# STM32_QFP100_DEVELOPMENT_BOARD.net
KiCad netlist of a schematic drawn in Altium Designer
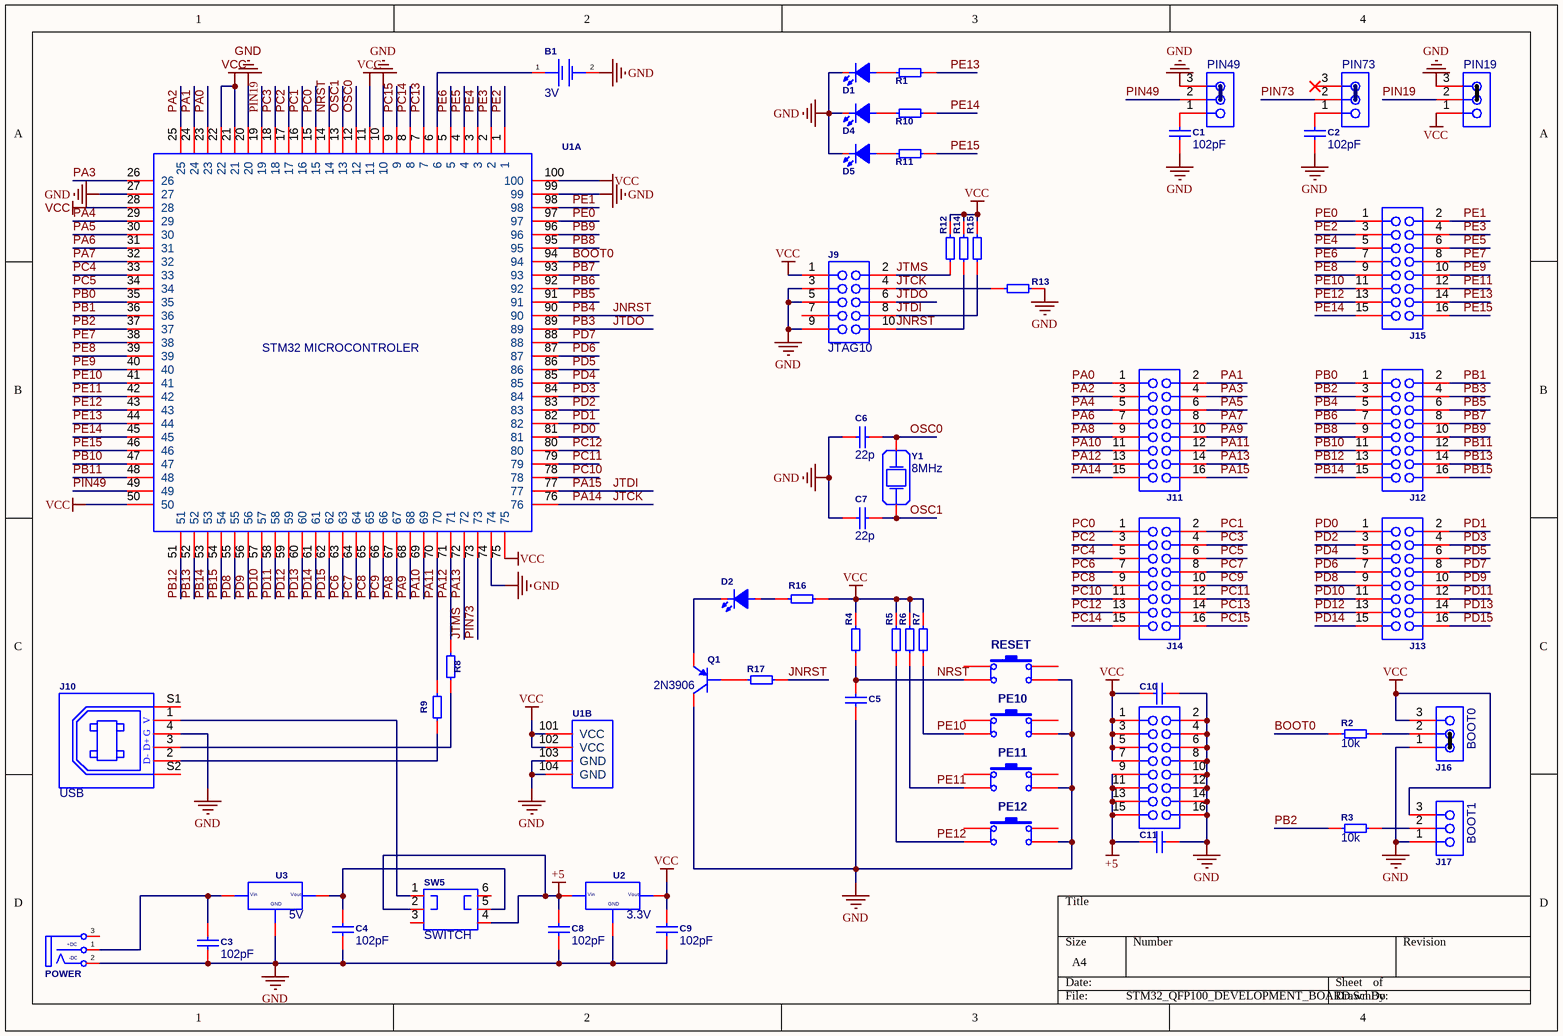
[diagram p0: STM32_QFP100_DEVELOPMENT_BOARD.SchDoc]

(export (version "E")
  (design (tool "Eeschema 10.0.6"))
  (components
    (comp (ref "B1") (value "3V") (footprint "CR1220") (libsource (lib "Lib31082020") (part "Batery")))
    (comp (ref "C1")
      (value "102pF")
      (footprint "C0805")
      (libsource (lib "Lib31082020") (part "Capacitors(SMD)"))
    )
    (comp (ref "C2")
      (value "102pF")
      (footprint "C0805")
      (libsource (lib "Lib31082020") (part "Capacitors(SMD)"))
    )
    (comp (ref "C3")
      (value "102pF")
      (footprint "C1206")
      (libsource (lib "Lib31082020") (part "Capacitors(SMD)"))
    )
    (comp (ref "C4")
      (value "102pF")
      (footprint "C1206")
      (libsource (lib "Lib31082020") (part "Capacitors(SMD)"))
    )
    (comp (ref "C5") (value "104P") (footprint "C0805") (libsource (lib "Lib31082020") (part "C0805")))
    (comp (ref "C6") (value "22p") (footprint "C0805") (libsource (lib "Lib31082020") (part "C0805")))
    (comp (ref "C7") (value "22p") (footprint "C0805") (libsource (lib "Lib31082020") (part "C0805")))
    (comp (ref "C8")
      (value "102pF")
      (footprint "C1206")
      (libsource (lib "Lib31082020") (part "Capacitors(SMD)"))
    )
    (comp (ref "C9")
      (value "102pF")
      (footprint "C1206")
      (libsource (lib "Lib31082020") (part "Capacitors(SMD)"))
    )
    (comp (ref "C10")
      (value "102pF")
      (footprint "C1206")
      (libsource (lib "Lib31082020") (part "Capacitors(SMD)"))
    )
    (comp (ref "C11")
      (value "102pF")
      (footprint "C1206")
      (libsource (lib "Lib31082020") (part "Capacitors(SMD)"))
    )
    (comp (ref "D1") (value "PE13") (footprint "L0805RED") (libsource (lib "Lib31082020") (part "LED0805")))
    (comp (ref "D2")
      (value "LED0805")
      (footprint "L0805RED")
      (libsource (lib "Lib31082020") (part "LED0805"))
    )
    (comp (ref "D4") (value "PE14") (footprint "L0805RED") (libsource (lib "Lib31082020") (part "LED0805")))
    (comp (ref "D5") (value "PE15") (footprint "L0805RED") (libsource (lib "Lib31082020") (part "LED0805")))
    (comp (ref "J1")
      (value "POWER")
      (footprint "Header 8x2 TH Pitch 2.54mm")
      (libsource (lib "Lib31082020") (part "Header 8x2 TH Pitch 2.54mm"))
    )
    (comp (ref "J3")
      (value "PIN19")
      (footprint "Header 3x1 TH Pitch 2.54mm")
      (libsource (lib "Lib31082020") (part "Header 3x1 TH Pitch 2.54mm"))
    )
    (comp (ref "J5")
      (value "PIN49")
      (footprint "Header 3x1 TH Pitch 2.54mm")
      (libsource (lib "Lib31082020") (part "Header 3x1 TH Pitch 2.54mm"))
    )
    (comp (ref "J6")
      (value "PIN73")
      (footprint "Header 3x1 TH Pitch 2.54mm")
      (libsource (lib "Lib31082020") (part "Header 3x1 TH Pitch 2.54mm"))
    )
    (comp (ref "J9")
      (value "JTAG10")
      (footprint "IDC_CONNECTOR_10x2.54")
      (libsource (lib "Lib31082020") (part "IDC_2.54_5x2"))
    )
    (comp (ref "J10")
      (value "USB")
      (footprint "USB-B-TYPE")
      (libsource (lib "Lib31082020") (part "USB B Type"))
    )
    (comp (ref "J11")
      (value "PORTA")
      (footprint "Header 8x2 TH Pitch 2.54mm")
      (libsource (lib "Lib31082020") (part "Header 8x2 TH Pitch 2.54mm"))
    )
    (comp (ref "J12")
      (value "PORTB")
      (footprint "Header 8x2 TH Pitch 2.54mm")
      (libsource (lib "Lib31082020") (part "Header 8x2 TH Pitch 2.54mm"))
    )
    (comp (ref "J13")
      (value "PORTD")
      (footprint "Header 8x2 TH Pitch 2.54mm")
      (libsource (lib "Lib31082020") (part "Header 8x2 TH Pitch 2.54mm"))
    )
    (comp (ref "J14")
      (value "PORTC")
      (footprint "Header 8x2 TH Pitch 2.54mm")
      (libsource (lib "Lib31082020") (part "Header 8x2 TH Pitch 2.54mm"))
    )
    (comp (ref "J15")
      (value "PORTE")
      (footprint "Header 8x2 TH Pitch 2.54mm")
      (libsource (lib "Lib31082020") (part "Header 8x2 TH Pitch 2.54mm"))
    )
    (comp (ref "J16")
      (value "BOOT0")
      (footprint "Header 3x1 TH Pitch 2.54mm")
      (libsource (lib "Lib31082020") (part "Header 3x1 TH Pitch 2.54mm"))
    )
    (comp (ref "J17")
      (value "BOOT1")
      (footprint "Header 3x1 TH Pitch 2.54mm")
      (libsource (lib "Lib31082020") (part "Header 3x1 TH Pitch 2.54mm"))
    )
    (comp (ref "POWER")
      (value "Connector")
      (footprint "DC_K375A_Power")
      (libsource (lib "Lib31082020") (part "JackDC"))
    )
    (comp (ref "Q1")
      (value "2N3906")
      (footprint "SOT23-3")
      (libsource (lib "Lib31082020") (part "2N3906 (SOT-23)"))
    )
    (comp (ref "R1") (value "10k") (footprint "R0805") (libsource (lib "") (part "Resistor SMD_1")))
    (comp (ref "R2") (value "10k") (footprint "R0805") (libsource (lib "") (part "Resistor SMD_2")))
    (comp (ref "R3") (value "10k") (footprint "R0805") (libsource (lib "") (part "Resistor SMD_2")))
    (comp (ref "R4") (value "4K7") (footprint "R0805") (libsource (lib "Lib31082020") (part "Resistor SMD")))
    (comp (ref "R5") (value "4K7") (footprint "R0805") (libsource (lib "Lib31082020") (part "Resistor SMD")))
    (comp (ref "R6") (value "4K7") (footprint "R0805") (libsource (lib "Lib31082020") (part "Resistor SMD")))
    (comp (ref "R7") (value "4K7") (footprint "R0805") (libsource (lib "Lib31082020") (part "Resistor SMD")))
    (comp (ref "R8") (value "4K7") (footprint "R0805") (libsource (lib "") (part "Resistor SMD_3")))
    (comp (ref "R9") (value "4K7") (footprint "R0805") (libsource (lib "") (part "Resistor SMD_3")))
    (comp (ref "R10") (value "10k") (footprint "R0805") (libsource (lib "") (part "Resistor SMD_1")))
    (comp (ref "R11") (value "10k") (footprint "R0805") (libsource (lib "") (part "Resistor SMD_1")))
    (comp (ref "R12") (value "10k") (footprint "R0805") (libsource (lib "Lib31082020") (part "Resistor SMD")))
    (comp (ref "R13") (value "10k") (footprint "R0805") (libsource (lib "") (part "Resistor SMD_2")))
    (comp (ref "R14") (value "10k") (footprint "R0805") (libsource (lib "Lib31082020") (part "Resistor SMD")))
    (comp (ref "R15") (value "10k") (footprint "R0805") (libsource (lib "Lib31082020") (part "Resistor SMD")))
    (comp (ref "R16") (value "1K") (footprint "R0805") (libsource (lib "") (part "Resistor SMD_1")))
    (comp (ref "R17") (value "4K7") (footprint "R0805") (libsource (lib "") (part "Resistor SMD_1")))
    (comp (ref "SW1")
      (value "RESET")
      (footprint "BUTTON_HOLE_5.0mm")
      (libsource (lib "Lib31082020") (part "Button Hole"))
    )
    (comp (ref "SW2")
      (value "PE10")
      (footprint "BUTTON_HOLE_5.0mm")
      (libsource (lib "Lib31082020") (part "Button Hole"))
    )
    (comp (ref "SW3")
      (value "PE11")
      (footprint "BUTTON_HOLE_5.0mm")
      (libsource (lib "Lib31082020") (part "Button Hole"))
    )
    (comp (ref "SW4")
      (value "PE12")
      (footprint "BUTTON_HOLE_5.0mm")
      (libsource (lib "Lib31082020") (part "Button Hole"))
    )
    (comp (ref "SW5")
      (value "SWITCH")
      (footprint "SWITCH 5.8x5.8 6 PINS")
      (libsource (lib "Lib31082020") (part "SWITCH-DPDT"))
    )
    (comp (ref "U1")
      (value "SOCKET-ADAPTER-OTQ-100-05-12")
      (footprint "SOCKET-ADAPTER-OTQ-100-05-12")
      (libsource (lib "") (part "SOCKET-ADAPTER-OTQ-100-05-12_1"))
    )
    (comp (ref "U2")
      (value "3.3V")
      (footprint "SOT223-3")
      (libsource (lib "Lib31082020") (part "AMS1117(SOT-223)"))
    )
    (comp (ref "U3")
      (value "5V")
      (footprint "SOT223-3")
      (libsource (lib "Lib31082020") (part "AMS1117(SOT-223)"))
    )
    (comp (ref "Y1") (value "8MHz") (footprint "HC-49S") (libsource (lib "Lib31082020") (part "Crystal")))
  )
  (nets
    (net (code "1") (name "+5") (class "Default")
      (node (ref "C11") (pin "2") (pinfunction "2_2") (pintype "passive"))
      (node (ref "C8") (pin "2") (pinfunction "2_2") (pintype "passive"))
      (node (ref "J1") (pin "11") (pinfunction "11_11") (pintype "passive"))
      (node (ref "J1") (pin "13") (pinfunction "13_13") (pintype "passive"))
      (node (ref "J1") (pin "15") (pinfunction "15_15") (pintype "passive"))
      (node (ref "J1") (pin "9") (pinfunction "9_9") (pintype "passive"))
      (node (ref "SW5") (pin "2") (pinfunction "2_2") (pintype "passive"))
      (node (ref "SW5") (pin "4") (pinfunction "4_4") (pintype "passive"))
      (node (ref "U2") (pin "3") (pinfunction "3_3") (pintype "passive"))
    )
    (net (code "2") (name "/BOOT0") (class "Default")
      (node (ref "R2") (pin "2") (pinfunction "2_2") (pintype "passive"))
      (node (ref "U1") (pin "94") (pinfunction "94_94") (pintype "passive"))
    )
    (net (code "3") (name "/JNRST") (class "Default")
      (node (ref "J12") (pin "5") (pinfunction "5_5") (pintype "passive"))
      (node (ref "J9") (pin "10") (pinfunction "10_10") (pintype "passive"))
      (node (ref "R14") (pin "2") (pinfunction "2_2") (pintype "passive"))
      (node (ref "R17") (pin "2") (pinfunction "2_2") (pintype "passive"))
      (node (ref "U1") (pin "90") (pinfunction "90_90") (pintype "passive"))
    )
    (net (code "4") (name "/JTCK") (class "Default")
      (node (ref "J11") (pin "15") (pinfunction "15_15") (pintype "passive"))
      (node (ref "J9") (pin "4") (pinfunction "4_4") (pintype "passive"))
      (node (ref "R13") (pin "2") (pinfunction "2_2") (pintype "passive"))
      (node (ref "U1") (pin "76") (pinfunction "76_76") (pintype "passive"))
    )
    (net (code "5") (name "/JTDI") (class "Default")
      (node (ref "J11") (pin "16") (pinfunction "16_16") (pintype "passive"))
      (node (ref "J9") (pin "8") (pinfunction "8_8") (pintype "passive"))
      (node (ref "R15") (pin "2") (pinfunction "2_2") (pintype "passive"))
      (node (ref "U1") (pin "77") (pinfunction "77_77") (pintype "passive"))
    )
    (net (code "6") (name "/JTDO") (class "Default")
      (node (ref "J12") (pin "4") (pinfunction "4_4") (pintype "passive"))
      (node (ref "J9") (pin "6") (pinfunction "6_6") (pintype "passive"))
      (node (ref "U1") (pin "89") (pinfunction "89_89") (pintype "passive"))
    )
    (net (code "7") (name "/JTMS") (class "Default")
      (node (ref "J11") (pin "14") (pinfunction "14_14") (pintype "passive"))
      (node (ref "J9") (pin "2") (pinfunction "2_2") (pintype "passive"))
      (node (ref "R12") (pin "2") (pinfunction "2_2") (pintype "passive"))
      (node (ref "U1") (pin "72") (pinfunction "72_72") (pintype "passive"))
    )
    (net (code "8") (name "/NRST") (class "Default")
      (node (ref "C5") (pin "2") (pinfunction "2_2") (pintype "passive"))
      (node (ref "R4") (pin "2") (pinfunction "2_2") (pintype "passive"))
      (node (ref "SW1") (pin "2") (pinfunction "2_2") (pintype "passive"))
      (node (ref "U1") (pin "14") (pinfunction "14_14") (pintype "passive"))
    )
    (net (code "9") (name "/OSC0") (class "Default")
      (node (ref "C6") (pin "2") (pinfunction "2_2") (pintype "passive"))
      (node (ref "U1") (pin "12") (pinfunction "12_12") (pintype "passive"))
      (node (ref "Y1") (pin "2") (pinfunction "2_2") (pintype "passive"))
    )
    (net (code "10") (name "/OSC1") (class "Default")
      (node (ref "C7") (pin "2") (pinfunction "2_2") (pintype "passive"))
      (node (ref "U1") (pin "13") (pinfunction "13_13") (pintype "passive"))
      (node (ref "Y1") (pin "1") (pinfunction "1_1") (pintype "passive"))
    )
    (net (code "11") (name "/PA0") (class "Default")
      (node (ref "J11") (pin "1") (pinfunction "1_1") (pintype "passive"))
      (node (ref "U1") (pin "23") (pinfunction "23_23") (pintype "passive"))
    )
    (net (code "12") (name "/PA1") (class "Default")
      (node (ref "J11") (pin "2") (pinfunction "2_2") (pintype "passive"))
      (node (ref "U1") (pin "24") (pinfunction "24_24") (pintype "passive"))
    )
    (net (code "13") (name "/PA2") (class "Default")
      (node (ref "J11") (pin "3") (pinfunction "3_3") (pintype "passive"))
      (node (ref "U1") (pin "25") (pinfunction "25_25") (pintype "passive"))
    )
    (net (code "14") (name "/PA3") (class "Default")
      (node (ref "J11") (pin "4") (pinfunction "4_4") (pintype "passive"))
      (node (ref "U1") (pin "26") (pinfunction "26_26") (pintype "passive"))
    )
    (net (code "15") (name "/PA4") (class "Default")
      (node (ref "J11") (pin "5") (pinfunction "5_5") (pintype "passive"))
      (node (ref "U1") (pin "29") (pinfunction "29_29") (pintype "passive"))
    )
    (net (code "16") (name "/PA5") (class "Default")
      (node (ref "J11") (pin "6") (pinfunction "6_6") (pintype "passive"))
      (node (ref "U1") (pin "30") (pinfunction "30_30") (pintype "passive"))
    )
    (net (code "17") (name "/PA6") (class "Default")
      (node (ref "J11") (pin "7") (pinfunction "7_7") (pintype "passive"))
      (node (ref "U1") (pin "31") (pinfunction "31_31") (pintype "passive"))
    )
    (net (code "18") (name "/PA7") (class "Default")
      (node (ref "J11") (pin "8") (pinfunction "8_8") (pintype "passive"))
      (node (ref "U1") (pin "32") (pinfunction "32_32") (pintype "passive"))
    )
    (net (code "19") (name "/PA8") (class "Default")
      (node (ref "J11") (pin "9") (pinfunction "9_9") (pintype "passive"))
      (node (ref "U1") (pin "67") (pinfunction "67_67") (pintype "passive"))
    )
    (net (code "20") (name "/PA9") (class "Default")
      (node (ref "J11") (pin "10") (pinfunction "10_10") (pintype "passive"))
      (node (ref "U1") (pin "68") (pinfunction "68_68") (pintype "passive"))
    )
    (net (code "21") (name "/PA10") (class "Default")
      (node (ref "J11") (pin "11") (pinfunction "11_11") (pintype "passive"))
      (node (ref "U1") (pin "69") (pinfunction "69_69") (pintype "passive"))
    )
    (net (code "22") (name "/PA11") (class "Default")
      (node (ref "J11") (pin "12") (pinfunction "12_12") (pintype "passive"))
      (node (ref "R9") (pin "2") (pinfunction "2_2") (pintype "passive"))
      (node (ref "U1") (pin "70") (pinfunction "70_70") (pintype "passive"))
    )
    (net (code "23") (name "/PA12") (class "Default")
      (node (ref "J11") (pin "13") (pinfunction "13_13") (pintype "passive"))
      (node (ref "R8") (pin "2") (pinfunction "2_2") (pintype "passive"))
      (node (ref "U1") (pin "71") (pinfunction "71_71") (pintype "passive"))
    )
    (net (code "24") (name "/PB0") (class "Default")
      (node (ref "J12") (pin "1") (pinfunction "1_1") (pintype "passive"))
      (node (ref "U1") (pin "35") (pinfunction "35_35") (pintype "passive"))
    )
    (net (code "25") (name "/PB1") (class "Default")
      (node (ref "J12") (pin "2") (pinfunction "2_2") (pintype "passive"))
      (node (ref "U1") (pin "36") (pinfunction "36_36") (pintype "passive"))
    )
    (net (code "26") (name "/PB2") (class "Default")
      (node (ref "J12") (pin "3") (pinfunction "3_3") (pintype "passive"))
      (node (ref "R3") (pin "2") (pinfunction "2_2") (pintype "passive"))
      (node (ref "U1") (pin "37") (pinfunction "37_37") (pintype "passive"))
    )
    (net (code "27") (name "/PB5") (class "Default")
      (node (ref "J12") (pin "6") (pinfunction "6_6") (pintype "passive"))
      (node (ref "U1") (pin "91") (pinfunction "91_91") (pintype "passive"))
    )
    (net (code "28") (name "/PB6") (class "Default")
      (node (ref "J12") (pin "7") (pinfunction "7_7") (pintype "passive"))
      (node (ref "U1") (pin "92") (pinfunction "92_92") (pintype "passive"))
    )
    (net (code "29") (name "/PB7") (class "Default")
      (node (ref "J12") (pin "8") (pinfunction "8_8") (pintype "passive"))
      (node (ref "U1") (pin "93") (pinfunction "93_93") (pintype "passive"))
    )
    (net (code "30") (name "/PB8") (class "Default")
      (node (ref "J12") (pin "9") (pinfunction "9_9") (pintype "passive"))
      (node (ref "U1") (pin "95") (pinfunction "95_95") (pintype "passive"))
    )
    (net (code "31") (name "/PB9") (class "Default")
      (node (ref "J12") (pin "10") (pinfunction "10_10") (pintype "passive"))
      (node (ref "U1") (pin "96") (pinfunction "96_96") (pintype "passive"))
    )
    (net (code "32") (name "/PB10") (class "Default")
      (node (ref "J12") (pin "11") (pinfunction "11_11") (pintype "passive"))
      (node (ref "U1") (pin "47") (pinfunction "47_47") (pintype "passive"))
    )
    (net (code "33") (name "/PB11") (class "Default")
      (node (ref "J12") (pin "12") (pinfunction "12_12") (pintype "passive"))
      (node (ref "U1") (pin "48") (pinfunction "48_48") (pintype "passive"))
    )
    (net (code "34") (name "/PB12") (class "Default")
      (node (ref "J12") (pin "13") (pinfunction "13_13") (pintype "passive"))
      (node (ref "U1") (pin "51") (pinfunction "51_51") (pintype "passive"))
    )
    (net (code "35") (name "/PB13") (class "Default")
      (node (ref "J12") (pin "14") (pinfunction "14_14") (pintype "passive"))
      (node (ref "U1") (pin "52") (pinfunction "52_52") (pintype "passive"))
    )
    (net (code "36") (name "/PB14") (class "Default")
      (node (ref "J12") (pin "15") (pinfunction "15_15") (pintype "passive"))
      (node (ref "U1") (pin "53") (pinfunction "53_53") (pintype "passive"))
    )
    (net (code "37") (name "/PB15") (class "Default")
      (node (ref "J12") (pin "16") (pinfunction "16_16") (pintype "passive"))
      (node (ref "U1") (pin "54") (pinfunction "54_54") (pintype "passive"))
    )
    (net (code "38") (name "/PC0") (class "Default")
      (node (ref "J14") (pin "1") (pinfunction "1_1") (pintype "passive"))
      (node (ref "U1") (pin "15") (pinfunction "15_15") (pintype "passive"))
    )
    (net (code "39") (name "/PC1") (class "Default")
      (node (ref "J14") (pin "2") (pinfunction "2_2") (pintype "passive"))
      (node (ref "U1") (pin "16") (pinfunction "16_16") (pintype "passive"))
    )
    (net (code "40") (name "/PC2") (class "Default")
      (node (ref "J14") (pin "3") (pinfunction "3_3") (pintype "passive"))
      (node (ref "U1") (pin "17") (pinfunction "17_17") (pintype "passive"))
    )
    (net (code "41") (name "/PC3") (class "Default")
      (node (ref "J14") (pin "4") (pinfunction "4_4") (pintype "passive"))
      (node (ref "U1") (pin "18") (pinfunction "18_18") (pintype "passive"))
    )
    (net (code "42") (name "/PC4") (class "Default")
      (node (ref "J14") (pin "5") (pinfunction "5_5") (pintype "passive"))
      (node (ref "U1") (pin "33") (pinfunction "33_33") (pintype "passive"))
    )
    (net (code "43") (name "/PC5") (class "Default")
      (node (ref "J14") (pin "6") (pinfunction "6_6") (pintype "passive"))
      (node (ref "U1") (pin "34") (pinfunction "34_34") (pintype "passive"))
    )
    (net (code "44") (name "/PC6") (class "Default")
      (node (ref "J14") (pin "7") (pinfunction "7_7") (pintype "passive"))
      (node (ref "U1") (pin "63") (pinfunction "63_63") (pintype "passive"))
    )
    (net (code "45") (name "/PC7") (class "Default")
      (node (ref "J14") (pin "8") (pinfunction "8_8") (pintype "passive"))
      (node (ref "U1") (pin "64") (pinfunction "64_64") (pintype "passive"))
    )
    (net (code "46") (name "/PC8") (class "Default")
      (node (ref "J14") (pin "9") (pinfunction "9_9") (pintype "passive"))
      (node (ref "U1") (pin "65") (pinfunction "65_65") (pintype "passive"))
    )
    (net (code "47") (name "/PC9") (class "Default")
      (node (ref "J14") (pin "10") (pinfunction "10_10") (pintype "passive"))
      (node (ref "U1") (pin "66") (pinfunction "66_66") (pintype "passive"))
    )
    (net (code "48") (name "/PC10") (class "Default")
      (node (ref "J14") (pin "11") (pinfunction "11_11") (pintype "passive"))
      (node (ref "U1") (pin "78") (pinfunction "78_78") (pintype "passive"))
    )
    (net (code "49") (name "/PC11") (class "Default")
      (node (ref "J14") (pin "12") (pinfunction "12_12") (pintype "passive"))
      (node (ref "U1") (pin "79") (pinfunction "79_79") (pintype "passive"))
    )
    (net (code "50") (name "/PC12") (class "Default")
      (node (ref "J14") (pin "13") (pinfunction "13_13") (pintype "passive"))
      (node (ref "U1") (pin "80") (pinfunction "80_80") (pintype "passive"))
    )
    (net (code "51") (name "/PC13") (class "Default")
      (node (ref "J14") (pin "14") (pinfunction "14_14") (pintype "passive"))
      (node (ref "U1") (pin "7") (pinfunction "7_7") (pintype "passive"))
    )
    (net (code "52") (name "/PC14") (class "Default")
      (node (ref "J14") (pin "15") (pinfunction "15_15") (pintype "passive"))
      (node (ref "U1") (pin "8") (pinfunction "8_8") (pintype "passive"))
    )
    (net (code "53") (name "/PC15") (class "Default")
      (node (ref "J14") (pin "16") (pinfunction "16_16") (pintype "passive"))
      (node (ref "U1") (pin "9") (pinfunction "9_9") (pintype "passive"))
    )
    (net (code "54") (name "/PD0") (class "Default")
      (node (ref "J13") (pin "1") (pinfunction "1_1") (pintype "passive"))
      (node (ref "U1") (pin "81") (pinfunction "81_81") (pintype "passive"))
    )
    (net (code "55") (name "/PD1") (class "Default")
      (node (ref "J13") (pin "2") (pinfunction "2_2") (pintype "passive"))
      (node (ref "U1") (pin "82") (pinfunction "82_82") (pintype "passive"))
    )
    (net (code "56") (name "/PD2") (class "Default")
      (node (ref "J13") (pin "3") (pinfunction "3_3") (pintype "passive"))
      (node (ref "U1") (pin "83") (pinfunction "83_83") (pintype "passive"))
    )
    (net (code "57") (name "/PD3") (class "Default")
      (node (ref "J13") (pin "4") (pinfunction "4_4") (pintype "passive"))
      (node (ref "U1") (pin "84") (pinfunction "84_84") (pintype "passive"))
    )
    (net (code "58") (name "/PD4") (class "Default")
      (node (ref "J13") (pin "5") (pinfunction "5_5") (pintype "passive"))
      (node (ref "U1") (pin "85") (pinfunction "85_85") (pintype "passive"))
    )
    (net (code "59") (name "/PD5") (class "Default")
      (node (ref "J13") (pin "6") (pinfunction "6_6") (pintype "passive"))
      (node (ref "U1") (pin "86") (pinfunction "86_86") (pintype "passive"))
    )
    (net (code "60") (name "/PD6") (class "Default")
      (node (ref "J13") (pin "7") (pinfunction "7_7") (pintype "passive"))
      (node (ref "U1") (pin "87") (pinfunction "87_87") (pintype "passive"))
    )
    (net (code "61") (name "/PD7") (class "Default")
      (node (ref "J13") (pin "8") (pinfunction "8_8") (pintype "passive"))
      (node (ref "U1") (pin "88") (pinfunction "88_88") (pintype "passive"))
    )
    (net (code "62") (name "/PD8") (class "Default")
      (node (ref "J13") (pin "9") (pinfunction "9_9") (pintype "passive"))
      (node (ref "U1") (pin "55") (pinfunction "55_55") (pintype "passive"))
    )
    (net (code "63") (name "/PD9") (class "Default")
      (node (ref "J13") (pin "10") (pinfunction "10_10") (pintype "passive"))
      (node (ref "U1") (pin "56") (pinfunction "56_56") (pintype "passive"))
    )
    (net (code "64") (name "/PD10") (class "Default")
      (node (ref "J13") (pin "11") (pinfunction "11_11") (pintype "passive"))
      (node (ref "U1") (pin "57") (pinfunction "57_57") (pintype "passive"))
    )
    (net (code "65") (name "/PD11") (class "Default")
      (node (ref "J13") (pin "12") (pinfunction "12_12") (pintype "passive"))
      (node (ref "U1") (pin "58") (pinfunction "58_58") (pintype "passive"))
    )
    (net (code "66") (name "/PD12") (class "Default")
      (node (ref "J13") (pin "13") (pinfunction "13_13") (pintype "passive"))
      (node (ref "U1") (pin "59") (pinfunction "59_59") (pintype "passive"))
    )
    (net (code "67") (name "/PD13") (class "Default")
      (node (ref "J13") (pin "14") (pinfunction "14_14") (pintype "passive"))
      (node (ref "U1") (pin "60") (pinfunction "60_60") (pintype "passive"))
    )
    (net (code "68") (name "/PD14") (class "Default")
      (node (ref "J13") (pin "15") (pinfunction "15_15") (pintype "passive"))
      (node (ref "U1") (pin "61") (pinfunction "61_61") (pintype "passive"))
    )
    (net (code "69") (name "/PD15") (class "Default")
      (node (ref "J13") (pin "16") (pinfunction "16_16") (pintype "passive"))
      (node (ref "U1") (pin "62") (pinfunction "62_62") (pintype "passive"))
    )
    (net (code "70") (name "/PE0") (class "Default")
      (node (ref "J15") (pin "1") (pinfunction "1_1") (pintype "passive"))
      (node (ref "U1") (pin "97") (pinfunction "97_97") (pintype "passive"))
    )
    (net (code "71") (name "/PE1") (class "Default")
      (node (ref "J15") (pin "2") (pinfunction "2_2") (pintype "passive"))
      (node (ref "U1") (pin "98") (pinfunction "98_98") (pintype "passive"))
    )
    (net (code "72") (name "/PE2") (class "Default")
      (node (ref "J15") (pin "3") (pinfunction "3_3") (pintype "passive"))
      (node (ref "U1") (pin "1") (pinfunction "1_1") (pintype "passive"))
    )
    (net (code "73") (name "/PE3") (class "Default")
      (node (ref "J15") (pin "4") (pinfunction "4_4") (pintype "passive"))
      (node (ref "U1") (pin "2") (pinfunction "2_2") (pintype "passive"))
    )
    (net (code "74") (name "/PE4") (class "Default")
      (node (ref "J15") (pin "5") (pinfunction "5_5") (pintype "passive"))
      (node (ref "U1") (pin "3") (pinfunction "3_3") (pintype "passive"))
    )
    (net (code "75") (name "/PE5") (class "Default")
      (node (ref "J15") (pin "6") (pinfunction "6_6") (pintype "passive"))
      (node (ref "U1") (pin "4") (pinfunction "4_4") (pintype "passive"))
    )
    (net (code "76") (name "/PE6") (class "Default")
      (node (ref "J15") (pin "7") (pinfunction "7_7") (pintype "passive"))
      (node (ref "U1") (pin "5") (pinfunction "5_5") (pintype "passive"))
    )
    (net (code "77") (name "/PE7") (class "Default")
      (node (ref "J15") (pin "8") (pinfunction "8_8") (pintype "passive"))
      (node (ref "U1") (pin "38") (pinfunction "38_38") (pintype "passive"))
    )
    (net (code "78") (name "/PE8") (class "Default")
      (node (ref "J15") (pin "9") (pinfunction "9_9") (pintype "passive"))
      (node (ref "U1") (pin "39") (pinfunction "39_39") (pintype "passive"))
    )
    (net (code "79") (name "/PE9") (class "Default")
      (node (ref "J15") (pin "10") (pinfunction "10_10") (pintype "passive"))
      (node (ref "U1") (pin "40") (pinfunction "40_40") (pintype "passive"))
    )
    (net (code "80") (name "/PE10") (class "Default")
      (node (ref "J15") (pin "11") (pinfunction "11_11") (pintype "passive"))
      (node (ref "R7") (pin "2") (pinfunction "2_2") (pintype "passive"))
      (node (ref "SW2") (pin "2") (pinfunction "2_2") (pintype "passive"))
      (node (ref "U1") (pin "41") (pinfunction "41_41") (pintype "passive"))
    )
    (net (code "81") (name "/PE11") (class "Default")
      (node (ref "J15") (pin "12") (pinfunction "12_12") (pintype "passive"))
      (node (ref "R6") (pin "2") (pinfunction "2_2") (pintype "passive"))
      (node (ref "SW3") (pin "2") (pinfunction "2_2") (pintype "passive"))
      (node (ref "U1") (pin "42") (pinfunction "42_42") (pintype "passive"))
    )
    (net (code "82") (name "/PE12") (class "Default")
      (node (ref "J15") (pin "13") (pinfunction "13_13") (pintype "passive"))
      (node (ref "R5") (pin "2") (pinfunction "2_2") (pintype "passive"))
      (node (ref "SW4") (pin "2") (pinfunction "2_2") (pintype "passive"))
      (node (ref "U1") (pin "43") (pinfunction "43_43") (pintype "passive"))
    )
    (net (code "83") (name "/PE13") (class "Default")
      (node (ref "J15") (pin "14") (pinfunction "14_14") (pintype "passive"))
      (node (ref "R1") (pin "2") (pinfunction "2_2") (pintype "passive"))
      (node (ref "U1") (pin "44") (pinfunction "44_44") (pintype "passive"))
    )
    (net (code "84") (name "/PE14") (class "Default")
      (node (ref "J15") (pin "15") (pinfunction "15_15") (pintype "passive"))
      (node (ref "R10") (pin "2") (pinfunction "2_2") (pintype "passive"))
      (node (ref "U1") (pin "45") (pinfunction "45_45") (pintype "passive"))
    )
    (net (code "85") (name "/PE15") (class "Default")
      (node (ref "J15") (pin "16") (pinfunction "16_16") (pintype "passive"))
      (node (ref "R11") (pin "2") (pinfunction "2_2") (pintype "passive"))
      (node (ref "U1") (pin "46") (pinfunction "46_46") (pintype "passive"))
    )
    (net (code "86") (name "/PIN19") (class "Default")
      (node (ref "J3") (pin "2") (pinfunction "2_2") (pintype "passive"))
      (node (ref "U1") (pin "19") (pinfunction "19_19") (pintype "passive"))
    )
    (net (code "87") (name "/PIN49") (class "Default")
      (node (ref "J5") (pin "2") (pinfunction "2_2") (pintype "passive"))
      (node (ref "U1") (pin "49") (pinfunction "49_49") (pintype "passive"))
    )
    (net (code "88") (name "/PIN73") (class "Default")
      (node (ref "J6") (pin "2") (pinfunction "2_2") (pintype "passive"))
      (node (ref "U1") (pin "73") (pinfunction "73_73") (pintype "passive"))
    )
    (net (code "89") (name "GND") (class "Default")
      (node (ref "B1") (pin "2") (pinfunction "2_2") (pintype "passive"))
      (node (ref "C1") (pin "1") (pinfunction "1_1") (pintype "passive"))
      (node (ref "C10") (pin "1") (pinfunction "1_1") (pintype "passive"))
      (node (ref "C11") (pin "1") (pinfunction "1_1") (pintype "passive"))
      (node (ref "C2") (pin "1") (pinfunction "1_1") (pintype "passive"))
      (node (ref "C3") (pin "1") (pinfunction "1_1") (pintype "passive"))
      (node (ref "C4") (pin "1") (pinfunction "1_1") (pintype "passive"))
      (node (ref "C5") (pin "1") (pinfunction "1_1") (pintype "passive"))
      (node (ref "C6") (pin "1") (pinfunction "1_1") (pintype "passive"))
      (node (ref "C7") (pin "1") (pinfunction "1_1") (pintype "passive"))
      (node (ref "C8") (pin "1") (pinfunction "1_1") (pintype "passive"))
      (node (ref "C9") (pin "1") (pinfunction "1_1") (pintype "passive"))
      (node (ref "D1") (pin "2") (pinfunction "K_2") (pintype "passive"))
      (node (ref "D4") (pin "2") (pinfunction "K_2") (pintype "passive"))
      (node (ref "D5") (pin "2") (pinfunction "K_2") (pintype "passive"))
      (node (ref "J1") (pin "10") (pinfunction "10_10") (pintype "passive"))
      (node (ref "J1") (pin "12") (pinfunction "12_12") (pintype "passive"))
      (node (ref "J1") (pin "14") (pinfunction "14_14") (pintype "passive"))
      (node (ref "J1") (pin "16") (pinfunction "16_16") (pintype "passive"))
      (node (ref "J1") (pin "2") (pinfunction "2_2") (pintype "passive"))
      (node (ref "J1") (pin "4") (pinfunction "4_4") (pintype "passive"))
      (node (ref "J1") (pin "6") (pinfunction "6_6") (pintype "passive"))
      (node (ref "J1") (pin "8") (pinfunction "8_8") (pintype "passive"))
      (node (ref "J10") (pin "4") (pinfunction "4_4") (pintype "passive"))
      (node (ref "J16") (pin "1") (pinfunction "1_1") (pintype "passive"))
      (node (ref "J17") (pin "1") (pinfunction "1_1") (pintype "passive"))
      (node (ref "J3") (pin "3") (pinfunction "3_3") (pintype "passive"))
      (node (ref "J5") (pin "3") (pinfunction "3_3") (pintype "passive"))
      (node (ref "J9") (pin "3") (pinfunction "3_3") (pintype "passive"))
      (node (ref "J9") (pin "5") (pinfunction "5_5") (pintype "passive"))
      (node (ref "J9") (pin "9") (pinfunction "9_9") (pintype "passive"))
      (node (ref "POWER") (pin "2") (pinfunction "DC-_2") (pintype "passive"))
      (node (ref "Q1") (pin "3") (pinfunction "C_3") (pintype "passive"))
      (node (ref "R13") (pin "1") (pinfunction "1_1") (pintype "passive"))
      (node (ref "SW1") (pin "4") (pinfunction "4_4") (pintype "passive"))
      (node (ref "SW2") (pin "4") (pinfunction "4_4") (pintype "passive"))
      (node (ref "SW3") (pin "4") (pinfunction "4_4") (pintype "passive"))
      (node (ref "SW4") (pin "4") (pinfunction "4_4") (pintype "passive"))
      (node (ref "U1") (pin "10") (pinfunction "10_10") (pintype "passive"))
      (node (ref "U1") (pin "103") (pinfunction "GND_103") (pintype "passive"))
      (node (ref "U1") (pin "104") (pinfunction "GND_104") (pintype "passive"))
      (node (ref "U1") (pin "20") (pinfunction "20_20") (pintype "passive"))
      (node (ref "U1") (pin "27") (pinfunction "27_27") (pintype "passive"))
      (node (ref "U1") (pin "74") (pinfunction "74_74") (pintype "passive"))
      (node (ref "U1") (pin "99") (pinfunction "99_99") (pintype "passive"))
      (node (ref "U2") (pin "1") (pinfunction "1_1") (pintype "passive"))
      (node (ref "U3") (pin "1") (pinfunction "1_1") (pintype "passive"))
    )
    (net (code "90") (name "Net-(B1-Pad1)") (class "Default")
      (node (ref "B1") (pin "1") (pinfunction "1_1") (pintype "passive"))
      (node (ref "U1") (pin "6") (pinfunction "6_6") (pintype "passive"))
    )
    (net (code "91") (name "Net-(C1-Pad2)") (class "Default")
      (node (ref "C1") (pin "2") (pinfunction "2_2") (pintype "passive"))
      (node (ref "J5") (pin "1") (pinfunction "1_1") (pintype "passive"))
    )
    (net (code "92") (name "Net-(C2-Pad2)") (class "Default")
      (node (ref "C2") (pin "2") (pinfunction "2_2") (pintype "passive"))
      (node (ref "J6") (pin "1") (pinfunction "1_1") (pintype "passive"))
    )
    (net (code "93") (name "Net-(C4-Pad2)") (class "Default")
      (node (ref "C4") (pin "2") (pinfunction "2_2") (pintype "passive"))
      (node (ref "SW5") (pin "5") (pinfunction "5_5") (pintype "passive"))
      (node (ref "U3") (pin "2") (pinfunction "2_2") (pintype "passive"))
    )
    (net (code "94") (name "Net-(D1-A)") (class "Default")
      (node (ref "D1") (pin "1") (pinfunction "A_1") (pintype "passive"))
      (node (ref "R1") (pin "1") (pinfunction "1_1") (pintype "passive"))
    )
    (net (code "95") (name "Net-(D2-A)") (class "Default")
      (node (ref "D2") (pin "1") (pinfunction "A_1") (pintype "passive"))
      (node (ref "R16") (pin "1") (pinfunction "1_1") (pintype "passive"))
    )
    (net (code "96") (name "Net-(D2-K)") (class "Default")
      (node (ref "D2") (pin "2") (pinfunction "K_2") (pintype "passive"))
      (node (ref "Q1") (pin "2") (pinfunction "E_2") (pintype "passive"))
    )
    (net (code "97") (name "Net-(D4-A)") (class "Default")
      (node (ref "D4") (pin "1") (pinfunction "A_1") (pintype "passive"))
      (node (ref "R10") (pin "1") (pinfunction "1_1") (pintype "passive"))
    )
    (net (code "98") (name "Net-(D5-A)") (class "Default")
      (node (ref "D5") (pin "1") (pinfunction "A_1") (pintype "passive"))
      (node (ref "R11") (pin "1") (pinfunction "1_1") (pintype "passive"))
    )
    (net (code "99") (name "Net-(J10-Pad1)") (class "Default")
      (node (ref "J10") (pin "1") (pinfunction "1_1") (pintype "passive"))
      (node (ref "SW5") (pin "1") (pinfunction "1_1") (pintype "passive"))
    )
    (net (code "100") (name "Net-(J10-Pad2)") (class "Default")
      (node (ref "J10") (pin "2") (pinfunction "2_2") (pintype "passive"))
      (node (ref "R9") (pin "1") (pinfunction "1_1") (pintype "passive"))
    )
    (net (code "101") (name "Net-(J10-Pad3)") (class "Default")
      (node (ref "J10") (pin "3") (pinfunction "3_3") (pintype "passive"))
      (node (ref "R8") (pin "1") (pinfunction "1_1") (pintype "passive"))
    )
    (net (code "102") (name "Net-(J16-Pad2)") (class "Default")
      (node (ref "J16") (pin "2") (pinfunction "2_2") (pintype "passive"))
      (node (ref "R2") (pin "1") (pinfunction "1_1") (pintype "passive"))
    )
    (net (code "103") (name "Net-(J17-Pad2)") (class "Default")
      (node (ref "J17") (pin "2") (pinfunction "2_2") (pintype "passive"))
      (node (ref "R3") (pin "1") (pinfunction "1_1") (pintype "passive"))
    )
    (net (code "104") (name "Net-(POWER-DS+)") (class "Default")
      (node (ref "C3") (pin "2") (pinfunction "2_2") (pintype "passive"))
      (node (ref "POWER") (pin "1") (pinfunction "DS+_1") (pintype "power_in"))
      (node (ref "U3") (pin "3") (pinfunction "3_3") (pintype "passive"))
    )
    (net (code "105") (name "Net-(Q1-B)") (class "Default")
      (node (ref "Q1") (pin "1") (pinfunction "B_1") (pintype "passive"))
      (node (ref "R17") (pin "1") (pinfunction "1_1") (pintype "passive"))
    )
    (net (code "106") (name "VCC") (class "Default")
      (node (ref "C10") (pin "2") (pinfunction "2_2") (pintype "passive"))
      (node (ref "C9") (pin "2") (pinfunction "2_2") (pintype "passive"))
      (node (ref "J1") (pin "1") (pinfunction "1_1") (pintype "passive"))
      (node (ref "J1") (pin "3") (pinfunction "3_3") (pintype "passive"))
      (node (ref "J1") (pin "5") (pinfunction "5_5") (pintype "passive"))
      (node (ref "J1") (pin "7") (pinfunction "7_7") (pintype "passive"))
      (node (ref "J16") (pin "3") (pinfunction "3_3") (pintype "passive"))
      (node (ref "J17") (pin "3") (pinfunction "3_3") (pintype "passive"))
      (node (ref "J3") (pin "1") (pinfunction "1_1") (pintype "passive"))
      (node (ref "J9") (pin "1") (pinfunction "1_1") (pintype "passive"))
      (node (ref "R12") (pin "1") (pinfunction "1_1") (pintype "passive"))
      (node (ref "R14") (pin "1") (pinfunction "1_1") (pintype "passive"))
      (node (ref "R15") (pin "1") (pinfunction "1_1") (pintype "passive"))
      (node (ref "R16") (pin "2") (pinfunction "2_2") (pintype "passive"))
      (node (ref "R4") (pin "1") (pinfunction "1_1") (pintype "passive"))
      (node (ref "R5") (pin "1") (pinfunction "1_1") (pintype "passive"))
      (node (ref "R6") (pin "1") (pinfunction "1_1") (pintype "passive"))
      (node (ref "R7") (pin "1") (pinfunction "1_1") (pintype "passive"))
      (node (ref "U1") (pin "100") (pinfunction "100_100") (pintype "passive"))
      (node (ref "U1") (pin "101") (pinfunction "VCC_101") (pintype "passive"))
      (node (ref "U1") (pin "102") (pinfunction "VCC_102") (pintype "passive"))
      (node (ref "U1") (pin "11") (pinfunction "11_11") (pintype "passive"))
      (node (ref "U1") (pin "21") (pinfunction "21_21") (pintype "passive"))
      (node (ref "U1") (pin "22") (pinfunction "22_22") (pintype "passive"))
      (node (ref "U1") (pin "28") (pinfunction "28_28") (pintype "passive"))
      (node (ref "U1") (pin "50") (pinfunction "50_50") (pintype "passive"))
      (node (ref "U1") (pin "75") (pinfunction "75_75") (pintype "passive"))
      (node (ref "U2") (pin "2") (pinfunction "2_2") (pintype "passive"))
    )
    (net (code "107") (name "unconnected-(J6-Pad3)") (class "Default")
      (node (ref "J6") (pin "3") (pinfunction "3_3") (pintype "passive+no_connect"))
    )
    (net (code "108") (name "unconnected-(J9-Pad7)") (class "Default")
      (node (ref "J9") (pin "7") (pinfunction "7_7") (pintype "passive"))
    )
    (net (code "109") (name "unconnected-(J10-PadS1)") (class "Default")
      (node (ref "J10") (pin "S1") (pinfunction "S1_S1") (pintype "passive"))
    )
    (net (code "110") (name "unconnected-(J10-PadS2)") (class "Default")
      (node (ref "J10") (pin "S2") (pinfunction "S2_S2") (pintype "passive"))
    )
    (net (code "111") (name "unconnected-(POWER-T-Pad3)") (class "Default")
      (node (ref "POWER") (pin "3") (pinfunction "T_3") (pintype "passive"))
    )
    (net (code "112") (name "unconnected-(SW1-Pad1)") (class "Default")
      (node (ref "SW1") (pin "1") (pinfunction "1_1") (pintype "passive"))
    )
    (net (code "113") (name "unconnected-(SW1-Pad3)") (class "Default")
      (node (ref "SW1") (pin "3") (pinfunction "3_3") (pintype "passive"))
    )
    (net (code "114") (name "unconnected-(SW2-Pad1)") (class "Default")
      (node (ref "SW2") (pin "1") (pinfunction "1_1") (pintype "passive"))
    )
    (net (code "115") (name "unconnected-(SW2-Pad3)") (class "Default")
      (node (ref "SW2") (pin "3") (pinfunction "3_3") (pintype "passive"))
    )
    (net (code "116") (name "unconnected-(SW3-Pad1)") (class "Default")
      (node (ref "SW3") (pin "1") (pinfunction "1_1") (pintype "passive"))
    )
    (net (code "117") (name "unconnected-(SW3-Pad3)") (class "Default")
      (node (ref "SW3") (pin "3") (pinfunction "3_3") (pintype "passive"))
    )
    (net (code "118") (name "unconnected-(SW4-Pad1)") (class "Default")
      (node (ref "SW4") (pin "1") (pinfunction "1_1") (pintype "passive"))
    )
    (net (code "119") (name "unconnected-(SW4-Pad3)") (class "Default")
      (node (ref "SW4") (pin "3") (pinfunction "3_3") (pintype "passive"))
    )
    (net (code "120") (name "unconnected-(SW5-Pad3)") (class "Default")
      (node (ref "SW5") (pin "3") (pinfunction "3_3") (pintype "passive"))
    )
    (net (code "121") (name "unconnected-(SW5-Pad6)") (class "Default")
      (node (ref "SW5") (pin "6") (pinfunction "6_6") (pintype "passive"))
    )
  )
)
